# Power_Management.net
KiCad netlist of a schematic drawn in Altium Designer
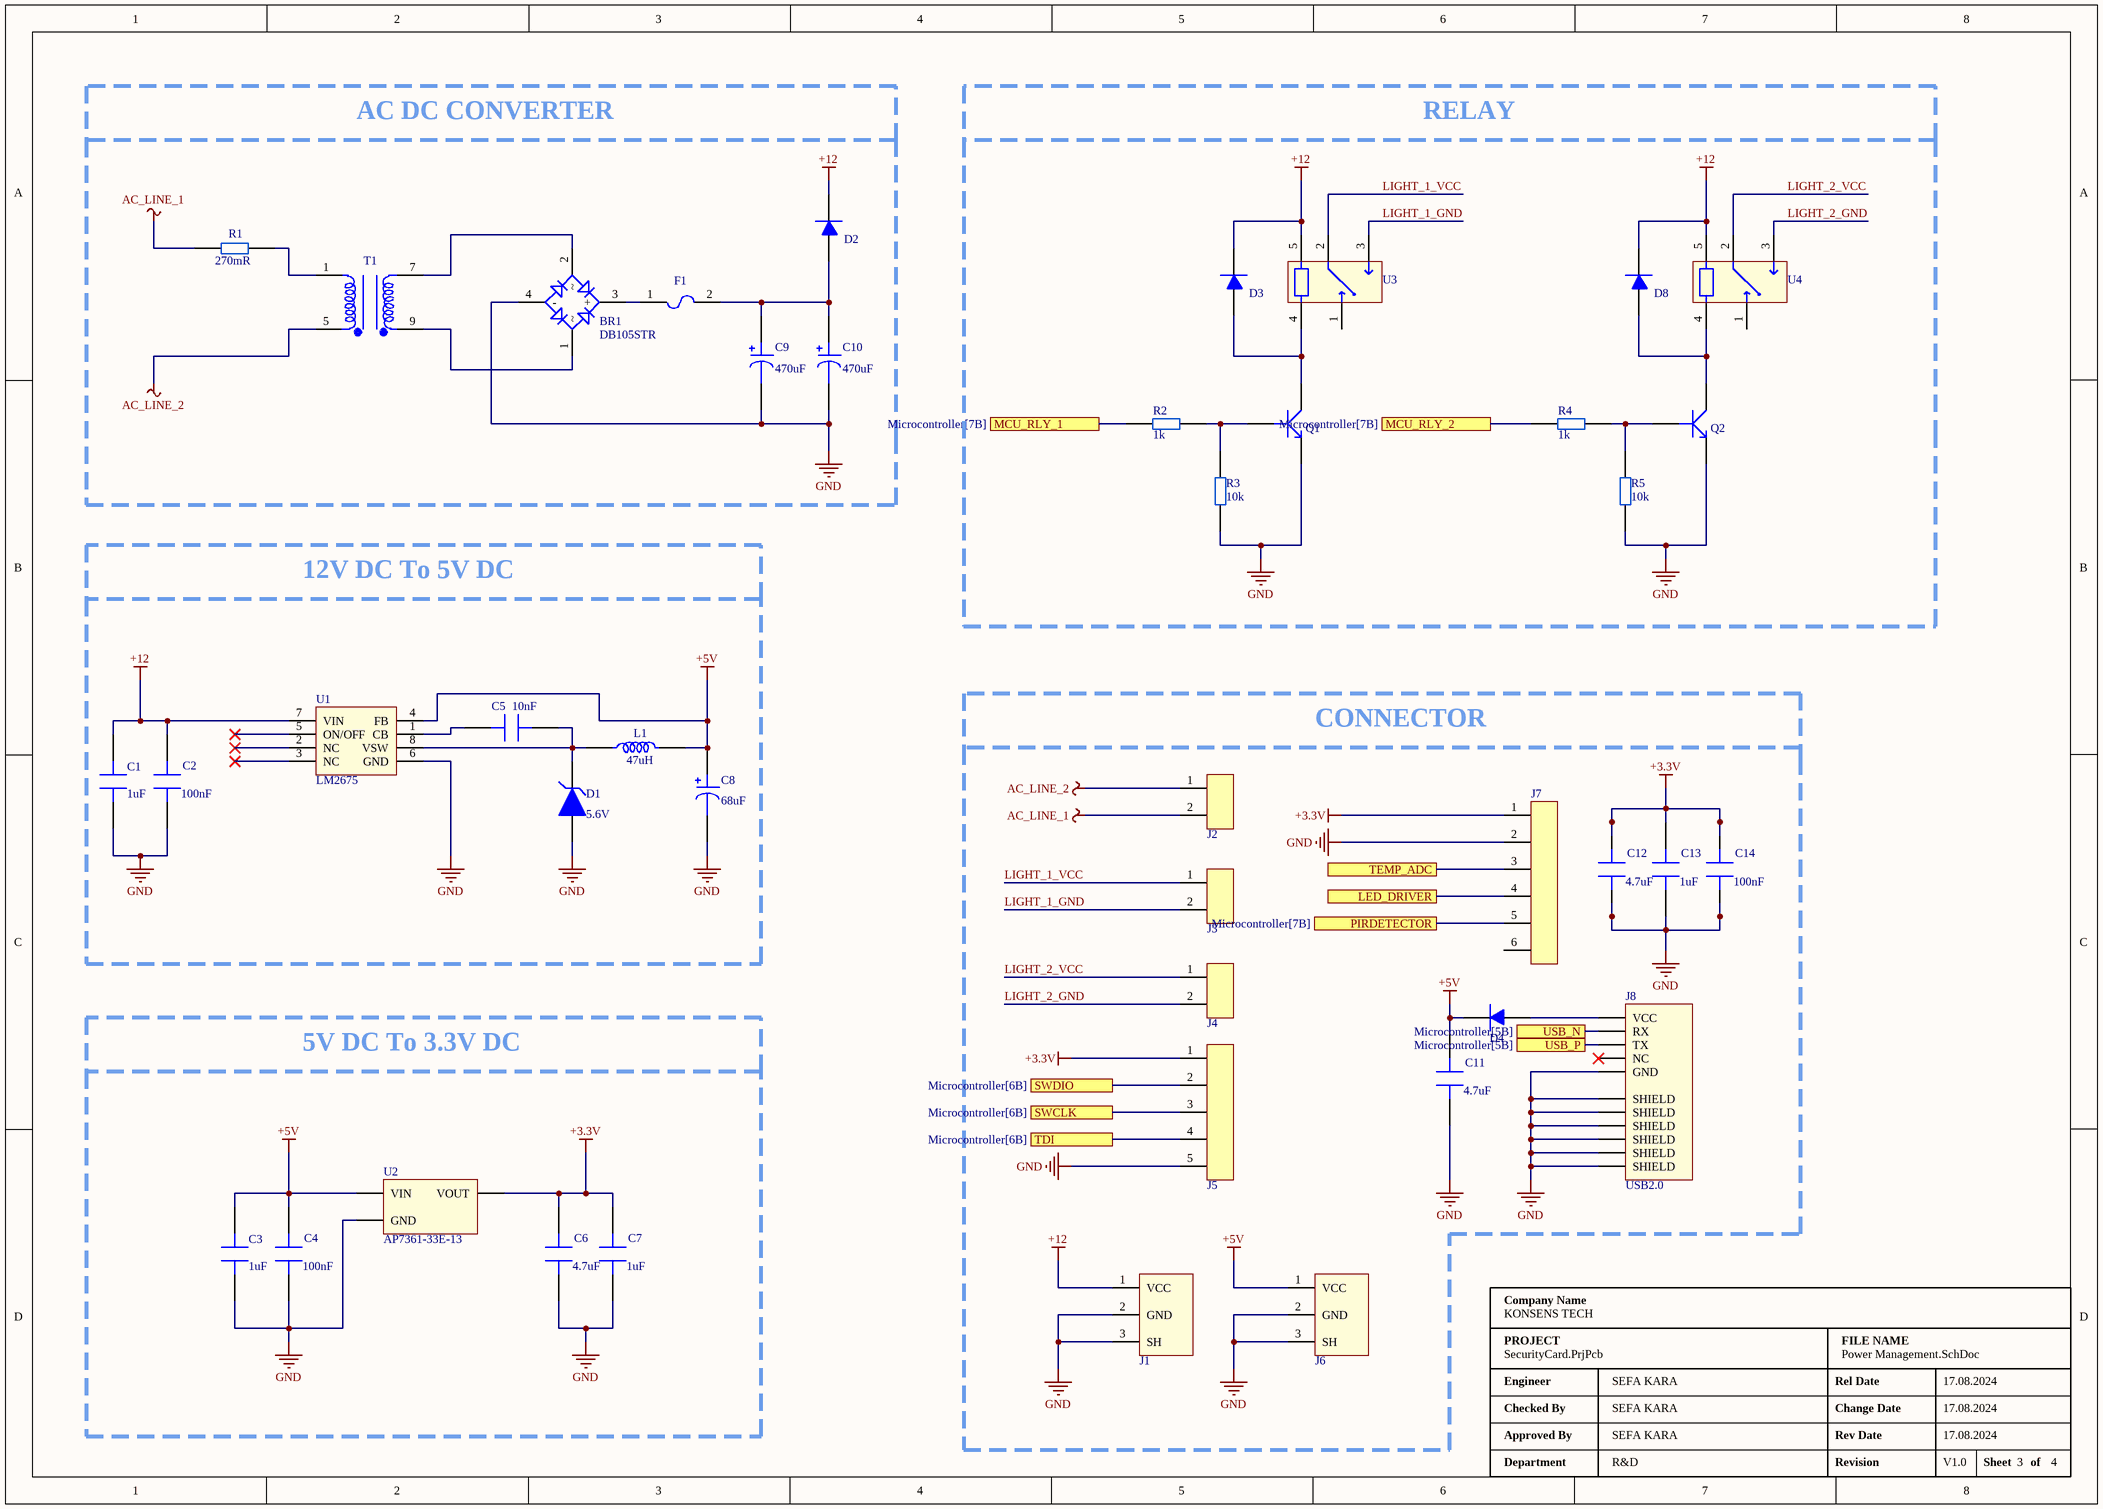
[diagram p0: Power Management.SchDoc]

(export (version "E")
  (design (tool "Eeschema 10.0.6"))
  (components
    (comp (ref "BR1")
      (value "DB105STR")
      (footprint "DB107S")
      (description "Bridge Rect 1PHASE 600V 1A Db-s")
      (fields (field (name "MANUFACTURER") "SMC") (field (name "DESIGNED BY") "SEFA"))
      (libsource (lib "SecurityLibray") (part "DB105STR"))
    )
    (comp (ref "C1")
      (value "1uF")
      (footprint "CAP 0805")
      (description "Multilayer Ceramic Capacitor, 1 uF, 25 V, ï¿½ 10%, X7R, 0805 [2012 Metric]")
      (fields
        (field (name "MANUFACTURER") "KEMET")
        (field (name "MANUFACTURER PART NUMBER") "C0805C105K3RACTU")
      )
      (libsource (lib "SecurityLibray") (part "CAP MLCC 1uF 0805 MLCC"))
    )
    (comp (ref "C2")
      (value "100nF")
      (footprint "CAP 0805")
      (description "Multilayer Ceramic Capacitor, 0.1 uF, 50 V, ± 10%, X7R, 0805 [2012 Metric]")
      (fields
        (field (name "MANUFACTURER") "Yageo")
        (field (name "MANUFACTURER PART NUMBER") "CC0805KRX7R9BB104")
      )
      (libsource (lib "SecurityLibray") (part "CAP MLCC 100nF 0805"))
    )
    (comp (ref "C3")
      (value "1uF")
      (footprint "CAP 0805")
      (description "Multilayer Ceramic Capacitor, 1 uF, 25 V, ï¿½ 10%, X7R, 0805 [2012 Metric]")
      (fields
        (field (name "MANUFACTURER") "KEMET")
        (field (name "MANUFACTURER PART NUMBER") "C0805C105K3RACTU")
      )
      (libsource (lib "SecurityLibray") (part "CAP MLCC 1uF 0805 MLCC"))
    )
    (comp (ref "C4")
      (value "100nF")
      (footprint "CAP 0805")
      (description "Multilayer Ceramic Capacitor, 0.1 uF, 50 V, ± 10%, X7R, 0805 [2012 Metric]")
      (fields
        (field (name "MANUFACTURER") "Yageo")
        (field (name "MANUFACTURER PART NUMBER") "CC0805KRX7R9BB104")
      )
      (libsource (lib "SecurityLibray") (part "CAP MLCC 100nF 0805"))
    )
    (comp (ref "C5")
      (value "10nF")
      (footprint "CAP 0603")
      (description "Multilayer Ceramic Capacitor, 0.01 uF, 50 V, ± 10%, X7R, 0603 [1608 Metric]")
      (fields
        (field (name "MANUFACTURER") "Yageo")
        (field (name "MANUFACTURER PART NUMBER") "CC0603KRX7R9BB103")
        (field (name "DESIGNED BY") "SEFA")
      )
      (libsource (lib "SecurityLibray") (part "CAP MLCC 10nF 0603"))
    )
    (comp (ref "C6")
      (value "4.7uF")
      (footprint "CAP 0805")
      (description "Multilayer Ceramic Capacitor, 4.7 uF, 25 V, ± 10%, X5R, 0805 [2012 Metric]")
      (fields
        (field (name "MANUFACTURER") "Samsung")
        (field (name "MANUFACTURER PART NUMBER") "CL21A475KAQNNNE")
        (field (name "DESIGNED BY") "SEFA")
      )
      (libsource (lib "SecurityLibray") (part "CAP MLCC 4.7uF 0805 MLCC"))
    )
    (comp (ref "C7")
      (value "1uF")
      (footprint "CAP 0805")
      (description "Multilayer Ceramic Capacitor, 1 uF, 25 V, ï¿½ 10%, X7R, 0805 [2012 Metric]")
      (fields
        (field (name "MANUFACTURER") "KEMET")
        (field (name "MANUFACTURER PART NUMBER") "C0805C105K3RACTU")
      )
      (libsource (lib "SecurityLibray") (part "CAP MLCC 1uF 0805 MLCC"))
    )
    (comp (ref "C8")
      (value "68uF")
      (footprint "CAP ALUM 68uF 20% 35V RADIAL TH")
      (description "68 µF 35 V Aluminum Electrolytic Capacitors Radial, Can 2000 Hrs @ 85°C")
      (fields
        (field (name "MANUFACTURER") "Wurth Electronics")
        (field (name "MANUFACTURER PART NUMBER") "860010573006")
        (field (name "DESIGNED BY") "SEFA")
      )
      (libsource (lib "SecurityLibray") (part "CAP 68uF 35V"))
    )
    (comp (ref "C9")
      (value "470uF")
      (footprint "CAP ALUM 470UF 20% 50V RADIAL TH")
      (description "Aluminum Electrolytic Capacitor, 470 uF, 63 V, ± 20%, 8000 hours @ 85°C, Axial Leaded")
      (fields
        (field (name "MANUFACTURER") "Vishay BCcomponents")
        (field (name "MANUFACTURER PART NUMBER") "MAL202118471E3")
      )
      (libsource (lib "SecurityLibray") (part "470uF ECAP CA-1HM471"))
    )
    (comp (ref "C10")
      (value "470uF")
      (footprint "CAP ALUM 470UF 20% 50V RADIAL TH")
      (description "Aluminum Electrolytic Capacitor, 470 uF, 63 V, ± 20%, 8000 hours @ 85°C, Axial Leaded")
      (fields
        (field (name "MANUFACTURER") "Vishay BCcomponents")
        (field (name "MANUFACTURER PART NUMBER") "MAL202118471E3")
      )
      (libsource (lib "SecurityLibray") (part "470uF ECAP CA-1HM471"))
    )
    (comp (ref "C11")
      (value "4.7uF")
      (footprint "CAP 0805")
      (description "Multilayer Ceramic Capacitor, 4.7 uF, 25 V, ± 10%, X5R, 0805 [2012 Metric]")
      (fields
        (field (name "MANUFACTURER") "Samsung")
        (field (name "MANUFACTURER PART NUMBER") "CL21A475KAQNNNE")
        (field (name "DESIGNED BY") "SEFA")
      )
      (libsource (lib "SecurityLibray") (part "CAP MLCC 4.7uF 0805 MLCC"))
    )
    (comp (ref "C12")
      (value "4.7uF")
      (footprint "CAP 0805")
      (description "Multilayer Ceramic Capacitor, 4.7 uF, 25 V, ± 10%, X5R, 0805 [2012 Metric]")
      (fields
        (field (name "MANUFACTURER") "Samsung")
        (field (name "MANUFACTURER PART NUMBER") "CL21A475KAQNNNE")
        (field (name "DESIGNED BY") "SEFA")
      )
      (libsource (lib "SecurityLibray") (part "CAP MLCC 4.7uF 0805 MLCC"))
    )
    (comp (ref "C13")
      (value "1uF")
      (footprint "CAP 0805")
      (description "Multilayer Ceramic Capacitor, 1 uF, 25 V, ï¿½ 10%, X7R, 0805 [2012 Metric]")
      (fields
        (field (name "MANUFACTURER") "KEMET")
        (field (name "MANUFACTURER PART NUMBER") "C0805C105K3RACTU")
      )
      (libsource (lib "SecurityLibray") (part "CAP MLCC 1uF 0805 MLCC"))
    )
    (comp (ref "C14")
      (value "100nF")
      (footprint "CAP 0805")
      (description "Multilayer Ceramic Capacitor, 0.1 uF, 50 V, ± 10%, X7R, 0805 [2012 Metric]")
      (fields
        (field (name "MANUFACTURER") "Yageo")
        (field (name "MANUFACTURER PART NUMBER") "CC0805KRX7R9BB104")
      )
      (libsource (lib "SecurityLibray") (part "CAP MLCC 100nF 0805"))
    )
    (comp (ref "D1")
      (value "DIODE ZENER 5.6V 3W SMB")
      (footprint "SMB")
      (description "Diode Zener Single 5.6V 5% 550mW Automotive 2-Pin SMB T/R")
      (fields
        (field (name "MANUFACTURER") "ON Semiconductor")
        (field (name "MANUFACTURER PART NUMBER") "1SMB5919BT3G")
        (field (name "VOLTAGE RATING (DC)") "5.6V")
        (field (name "DESIGNED BY") "SEFA")
      )
      (libsource (lib "SecurityLibray") (part "1SMB5919BT3G ZENER DIODE"))
    )
    (comp (ref "D2")
      (value "DIODE GEN PURP 75V 150MA SOD323F")
      (footprint "DIODE SOD323F")
      (description "Diode Ultra Fast Recovery Rectifier 75V 0.15A 2-Pin SOD-323F T/R")
      (fields
        (field (name "MANUFACTURER") "ON Semiconductor / Fairchild")
        (field (name "MANUFACTURER PART NUMBER") "1N4148WS")
      )
      (libsource (lib "SecurityLibray") (part "DIODE 1N4148WS"))
    )
    (comp (ref "D3")
      (value "DIODE GEN PURP 75V 150MA SOD323F")
      (footprint "DIODE SOD323F")
      (description "Diode Ultra Fast Recovery Rectifier 75V 0.15A 2-Pin SOD-323F T/R")
      (fields
        (field (name "MANUFACTURER") "ON Semiconductor / Fairchild")
        (field (name "MANUFACTURER PART NUMBER") "1N4148WS")
      )
      (libsource (lib "SecurityLibray") (part "DIODE 1N4148WS"))
    )
    (comp (ref "D4")
      (value "DIODE GEN PURP 75V 150MA SOD323F")
      (footprint "DIODE SOD323F")
      (description "Diode Ultra Fast Recovery Rectifier 75V 0.15A 2-Pin SOD-323F T/R")
      (fields
        (field (name "MANUFACTURER") "ON Semiconductor / Fairchild")
        (field (name "MANUFACTURER PART NUMBER") "1N4148WS")
      )
      (libsource (lib "SecurityLibray") (part "DIODE 1N4148WS"))
    )
    (comp (ref "D8")
      (value "DIODE GEN PURP 75V 150MA SOD323F")
      (footprint "DIODE SOD323F")
      (description "Diode Ultra Fast Recovery Rectifier 75V 0.15A 2-Pin SOD-323F T/R")
      (fields
        (field (name "MANUFACTURER") "ON Semiconductor / Fairchild")
        (field (name "MANUFACTURER PART NUMBER") "1N4148WS")
      )
      (libsource (lib "SecurityLibray") (part "DIODE 1N4148WS"))
    )
    (comp (ref "F1")
      (value "FUSE BRD MNT 1A 32VAC 63VDC 1206")
      (footprint "FUSE 1206 SMD")
      (description "Fuse Chip Fast Acting 1A 32V SMD Solder Pad 1206 Glass T/R VDE/cULus")
      (fields
        (field (name "MANUFACTURER") "Schurter")
        (field (name "MANUFACTURER PART NUMBER") "3413.0216.22")
        (field (name "DESIGNED BY") "SEFA")
      )
      (libsource (lib "SecurityLibray") (part "FUSE 3413.0216.22"))
    )
    (comp (ref "J1")
      (value "CONN PWR JACK 2X5.5MM SOLDER")
      (footprint "POWER JACK")
      (description "2.0 x 6.3 mm, 5.0 A, Horizontal, Surface Mount (SMT), Dc Power Jack Connector")
      (fields
        (field (name "MANUFACTURER") "CUI")
        (field (name "MANUFACTURER PART NUMBER") "PJ-037AH-SMT-TR")
        (field (name "DESIGNED BY") "SEFA")
      )
      (libsource (lib "SecurityLibray") (part "JACK CONN PJ-037AH-SMT-TR"))
    )
    (comp (ref "J2")
      (value "TERMINAL BLOCK, PLUGGABLE, 5.08,")
      (footprint "TERMINAL 2P 508")
      (description "2~24 Poles, Pluggable, Receptacle, Horizontal, 5.08 Pitch, Terminal Block Connector")
      (fields
        (field (name "MANUFACTURER") "CUI Devices")
        (field (name "MANUFACTURER PART NUMBER") "TBP01R1-508-02BE")
        (field (name "DESIGNED BY") "SEFA")
      )
      (libsource (lib "SecurityLibray") (part "2P TERMINAL TBP01R1-508-02BE"))
    )
    (comp (ref "J3")
      (value "TERMINAL BLOCK, PLUGGABLE, 5.08,")
      (footprint "TERMINAL 2P 508")
      (description "2~24 Poles, Pluggable, Receptacle, Horizontal, 5.08 Pitch, Terminal Block Connector")
      (fields
        (field (name "MANUFACTURER") "CUI Devices")
        (field (name "MANUFACTURER PART NUMBER") "TBP01R1-508-02BE")
        (field (name "DESIGNED BY") "SEFA")
      )
      (libsource (lib "SecurityLibray") (part "2P TERMINAL TBP01R1-508-02BE"))
    )
    (comp (ref "J4")
      (value "TERMINAL BLOCK, PLUGGABLE, 5.08,")
      (footprint "TERMINAL 2P 508")
      (description "2~24 Poles, Pluggable, Receptacle, Horizontal, 5.08 Pitch, Terminal Block Connector")
      (fields
        (field (name "MANUFACTURER") "CUI Devices")
        (field (name "MANUFACTURER PART NUMBER") "TBP01R1-508-02BE")
        (field (name "DESIGNED BY") "SEFA")
      )
      (libsource (lib "SecurityLibray") (part "2P TERMINAL TBP01R1-508-02BE"))
    )
    (comp (ref "J5")
      (value "CONN RCPT 5POS 0.1 GOLD SMD R/A")
      (footprint "PIN HEADER 5P 2.54mm MH-105-02-L-S")
      (description "PCB Receptacle, Board-to-Board, 2.54 mm, 1 Rows, 5 Contacts, Surface Mount, SMH")
      (fields
        (field (name "MANUFACTURER") "Samtec")
        (field (name "MANUFACTURER PART NUMBER") "SMH-105-02-L-S")
        (field (name "DESIGNED BY") "SEFA")
      )
      (libsource (lib "SecurityLibray") (part "PIN HEADER 2.54mm SMH-105-02-L-S"))
    )
    (comp (ref "J6")
      (value "CONN PWR JACK 2X5.5MM SOLDER")
      (footprint "POWER JACK")
      (description "2.0 x 6.3 mm, 5.0 A, Horizontal, Surface Mount (SMT), Dc Power Jack Connector")
      (fields
        (field (name "MANUFACTURER") "CUI")
        (field (name "MANUFACTURER PART NUMBER") "PJ-037AH-SMT-TR")
        (field (name "DESIGNED BY") "SEFA")
      )
      (libsource (lib "SecurityLibray") (part "JACK CONN PJ-037AH-SMT-TR"))
    )
    (comp (ref "J7")
      (value "CONN HEADER VERT 6POS 1.5MM")
      (footprint "TUNIK 6P 2.5mm")
      (description "Header B6B-ZR, 1.50mm, 6-contacts, top entry, THT, /2000/box")
      (fields
        (field (name "MANUFACTURER") "JST")
        (field (name "MANUFACTURER PART NUMBER") "B6B-ZR")
        (field (name "DESIGNED BY") "SEFA")
      )
      (libsource (lib "SecurityLibray") (part "TUNIK 6P 2.5mm"))
    )
    (comp (ref "J8")
      (value "USB2.0")
      (footprint "MICRO B USB CONN")
      (description "CONN USB MICRO B RECPT SMT R/A")
      (fields
        (field (name "MANUFACTURER") "Amphenol ICC / FCI")
        (field (name "MANUFACTURER PART NUMBER") "10118192-0001LF")
        (field (name "DESIGNED BY") "SEFA")
      )
      (libsource (lib "SecurityLibray") (part "MICRO B USB CONN"))
    )
    (comp (ref "L1")
      (value "47uH")
      (footprint "IND 1212")
      (description "Power Inductor, Aec-Q200, 47Uh, 0.39A Rohs Compliant: Yes ¦Wurth Elektronik 78438335470")
      (fields
        (field (name "MANUFACTURER") "Wurth Electronics")
        (field (name "MANUFACTURER PART NUMBER") "78438335470")
        (field (name "DESIGNED BY") "SEFA")
      )
      (libsource (lib "SecurityLibray") (part "IND 47uH"))
    )
    (comp (ref "Q1")
      (value "TRANS NPN 40V 0.2A SOT23")
      (footprint "SOT-23-3")
      (description "Transistor: NPN; bipolar; 40V; 0.2A; 350mW; -55+150 deg.C; SMD; SOT23")
      (fields
        (field (name "MANUFACTURER") "Diotec")
        (field (name "MANUFACTURER PART NUMBER") "MMBT3904")
        (field (name "DESIGNED BY") "SEFA")
      )
      (libsource (lib "SecurityLibray") (part "MMBT3904 NPN TR"))
    )
    (comp (ref "Q2")
      (value "TRANS NPN 40V 0.2A SOT23")
      (footprint "SOT-23-3")
      (description "Transistor: NPN; bipolar; 40V; 0.2A; 350mW; -55+150 deg.C; SMD; SOT23")
      (fields
        (field (name "MANUFACTURER") "Diotec")
        (field (name "MANUFACTURER PART NUMBER") "MMBT3904")
        (field (name "DESIGNED BY") "SEFA")
      )
      (libsource (lib "SecurityLibray") (part "MMBT3904 NPN TR"))
    )
    (comp (ref "R1")
      (value "270mR")
      (footprint "SQP500JB-10R")
      (description "270 mOhms ±5% 5W Through Hole Resistor Axial Wirewound")
      (fields (field (name "Comment") "RES 0.27 OHM 5% 5W AXIAL"))
      (libsource (lib "SecurityLibray") (part "RES 270mR 5WD27"))
    )
    (comp (ref "R2")
      (value "1k")
      (footprint "RES 0603")
      (description "Res Thick Film 0603 10K Ohm 5% 1/10W ±100ppm/°C Molded SMD SMD Paper T/R")
      (fields
        (field (name "MANUFACTURER") "Stackpole Electronics")
        (field (name "MANUFACTURER PART NUMBER") "RMCF0603JT10K0")
        (field (name "DESIGNED BY") "SEFA")
      )
      (libsource (lib "") (part "RES 10K OHM 0603_1"))
    )
    (comp (ref "R3")
      (value "10k")
      (footprint "RES 0603")
      (description "Res Thick Film 0603 10K Ohm 5% 1/10W ±100ppm/°C Molded SMD SMD Paper T/R")
      (fields
        (field (name "MANUFACTURER") "Stackpole Electronics")
        (field (name "MANUFACTURER PART NUMBER") "RMCF0603JT10K0")
        (field (name "DESIGNED BY") "SEFA")
      )
      (libsource (lib "SecurityLibray") (part "RES 10K OHM 0603"))
    )
    (comp (ref "R4")
      (value "1k")
      (footprint "RES 0603")
      (description "Res Thick Film 0603 10K Ohm 5% 1/10W ±100ppm/°C Molded SMD SMD Paper T/R")
      (fields
        (field (name "MANUFACTURER") "Stackpole Electronics")
        (field (name "MANUFACTURER PART NUMBER") "RMCF0603JT10K0")
        (field (name "DESIGNED BY") "SEFA")
      )
      (libsource (lib "") (part "RES 10K OHM 0603_1"))
    )
    (comp (ref "R5")
      (value "10k")
      (footprint "RES 0603")
      (description "Res Thick Film 0603 10K Ohm 5% 1/10W ±100ppm/°C Molded SMD SMD Paper T/R")
      (fields
        (field (name "MANUFACTURER") "Stackpole Electronics")
        (field (name "MANUFACTURER PART NUMBER") "RMCF0603JT10K0")
        (field (name "DESIGNED BY") "SEFA")
      )
      (libsource (lib "SecurityLibray") (part "RES 10K OHM 0603"))
    )
    (comp (ref "T1")
      (value "BV302S12010-ZU")
      (footprint "BV302S")
      (description "Sealed Transformer EI30/10.5")
      (fields
        (field (name "MANUFACTURER") "Zettler Magnetics")
        (field (name "MANUFACTURER PART NUMBER") "BV302S12010")
      )
      (libsource (lib "SecurityLibray") (part "BV302S12010-ZU"))
    )
    (comp (ref "U1")
      (value "LM2675")
      (footprint "SOIC8")
      (description "SIMPLE SWITCHER® 6.5V to 40V, 1A Low Component Count Step-Down Regulator 8-SOIC -40 to 125")
      (fields
        (field (name "MANUFACTURER") "TI National Semiconductor")
        (field (name "MANUFACTURER PART NUMBER") "LM2675M-5.0")
        (field (name "DESIGNED BY") "SEFA")
      )
      (libsource (lib "SecurityLibray") (part "LM2675"))
    )
    (comp (ref "U2")
      (value "AP7361-33E-13")
      (footprint "SOT223")
      (description "AP7361 Series 3.3 V 1 A Low SMT Dropout Fixed-Mode Regulator - SOT-223")
      (fields (field (name "MANUFACTURER") "Diodes") (field (name "DESIGNED BY") "SEFA"))
      (libsource (lib "SecurityLibray") (part "AP7361-33E-13"))
    )
    (comp (ref "U3")
      (value "ALQ112")
      (footprint "RELAY ALQ112")
      (description "Electromechanical Relay 12VDC 360Ohm 10(NO)/3(NC)A SPDT (( 20mm 10mm 16mm)) THT Power Relay")
      (fields (field (name "MANUFACTURER") "Panasonic") (field (name "DESIGNED BY") "SEFA"))
      (libsource (lib "SecurityLibray") (part "ALQ112"))
    )
    (comp (ref "U4")
      (value "ALQ112")
      (footprint "RELAY ALQ112")
      (description "Electromechanical Relay 12VDC 360Ohm 10(NO)/3(NC)A SPDT (( 20mm 10mm 16mm)) THT Power Relay")
      (fields (field (name "MANUFACTURER") "Panasonic") (field (name "DESIGNED BY") "SEFA"))
      (libsource (lib "SecurityLibray") (part "ALQ112"))
    )
  )
  (nets
    (net (code "1") (name "+3.3V") (class "Default")
      (node (ref "C12") (pin "2") (pinfunction "2_2") (pintype "passive"))
      (node (ref "C13") (pin "2") (pinfunction "2_2") (pintype "passive"))
      (node (ref "C14") (pin "2") (pinfunction "2_2") (pintype "passive"))
      (node (ref "C6") (pin "1") (pinfunction "1_1") (pintype "passive"))
      (node (ref "C7") (pin "2") (pinfunction "2_2") (pintype "passive"))
      (node (ref "J5") (pin "1") (pinfunction "1_1") (pintype "passive"))
      (node (ref "J7") (pin "1") (pintype "passive"))
      (node (ref "U2") (pin "3") (pinfunction "VOUT_3") (pintype "passive"))
    )
    (net (code "2") (name "+5V") (class "Default")
      (node (ref "C11") (pin "2") (pinfunction "2_2") (pintype "passive"))
      (node (ref "C3") (pin "2") (pinfunction "2_2") (pintype "passive"))
      (node (ref "C4") (pin "2") (pinfunction "2_2") (pintype "passive"))
      (node (ref "C8") (pin "1") (pinfunction "1_1") (pintype "passive"))
      (node (ref "D4") (pin "C") (pinfunction "2_C") (pintype "passive"))
      (node (ref "J6") (pin "1") (pinfunction "VCC_1") (pintype "passive"))
      (node (ref "L1") (pin "2") (pinfunction "2_2") (pintype "passive"))
      (node (ref "U1") (pin "4") (pinfunction "FB_4") (pintype "passive"))
      (node (ref "U2") (pin "1") (pinfunction "VIN_1") (pintype "passive"))
    )
    (net (code "3") (name "+12") (class "Default")
      (node (ref "C1") (pin "2") (pinfunction "2_2") (pintype "passive"))
      (node (ref "C2") (pin "2") (pinfunction "2_2") (pintype "passive"))
      (node (ref "D2") (pin "C") (pinfunction "2_C") (pintype "passive"))
      (node (ref "D3") (pin "C") (pinfunction "2_C") (pintype "passive"))
      (node (ref "D8") (pin "C") (pinfunction "2_C") (pintype "passive"))
      (node (ref "J1") (pin "1") (pinfunction "VCC_1") (pintype "passive"))
      (node (ref "U1") (pin "7") (pinfunction "VIN_7") (pintype "passive"))
      (node (ref "U3") (pin "5") (pinfunction "5_5") (pintype "passive"))
      (node (ref "U4") (pin "5") (pinfunction "5_5") (pintype "passive"))
    )
    (net (code "4") (name "/LED_DRIVER") (class "Default") (node (ref "J7") (pin "4") (pintype "passive")))
    (net (code "5") (name "/LIGHT_1_GND") (class "Default")
      (node (ref "J3") (pin "2") (pinfunction "2_2") (pintype "passive"))
      (node (ref "U3") (pin "3") (pinfunction "3_3") (pintype "passive"))
    )
    (net (code "6") (name "/LIGHT_1_VCC") (class "Default")
      (node (ref "J3") (pin "1") (pinfunction "1_1") (pintype "passive"))
      (node (ref "U3") (pin "2") (pinfunction "2_2") (pintype "passive"))
    )
    (net (code "7") (name "/LIGHT_2_GND") (class "Default")
      (node (ref "J4") (pin "2") (pinfunction "2_2") (pintype "passive"))
      (node (ref "U4") (pin "3") (pinfunction "3_3") (pintype "passive"))
    )
    (net (code "8") (name "/LIGHT_2_VCC") (class "Default")
      (node (ref "J4") (pin "1") (pinfunction "1_1") (pintype "passive"))
      (node (ref "U4") (pin "2") (pinfunction "2_2") (pintype "passive"))
    )
    (net (code "9") (name "/MCU_RLY_1") (class "Default")
      (node (ref "R2") (pin "2") (pinfunction "2_2") (pintype "passive"))
    )
    (net (code "10") (name "/MCU_RLY_2") (class "Default")
      (node (ref "R4") (pin "2") (pinfunction "2_2") (pintype "passive"))
    )
    (net (code "11") (name "/PIRDETECTOR") (class "Default") (node (ref "J7") (pin "5") (pintype "passive")))
    (net (code "12") (name "/SWCLK") (class "Default")
      (node (ref "J5") (pin "3") (pinfunction "3_3") (pintype "passive"))
    )
    (net (code "13") (name "/SWDIO") (class "Default")
      (node (ref "J5") (pin "2") (pinfunction "2_2") (pintype "passive"))
    )
    (net (code "14") (name "/TDI") (class "Default")
      (node (ref "J5") (pin "4") (pinfunction "4_4") (pintype "passive"))
    )
    (net (code "15") (name "/TEMP_ADC") (class "Default") (node (ref "J7") (pin "3") (pintype "passive")))
    (net (code "16") (name "/USB_N") (class "Default")
      (node (ref "J8") (pin "2") (pinfunction "RX_2") (pintype "passive"))
    )
    (net (code "17") (name "/USB_P") (class "Default")
      (node (ref "J8") (pin "3") (pinfunction "TX_3") (pintype "passive"))
    )
    (net (code "18") (name "AC_LINE_1") (class "Default")
      (node (ref "J2") (pin "2") (pinfunction "2_2") (pintype "passive"))
      (node (ref "R1") (pin "1") (pinfunction "1_1") (pintype "passive"))
    )
    (net (code "19") (name "AC_LINE_2") (class "Default")
      (node (ref "J2") (pin "1") (pinfunction "1_1") (pintype "passive"))
      (node (ref "T1") (pin "5") (pinfunction "5_5") (pintype "passive"))
    )
    (net (code "20") (name "GND") (class "Default")
      (node (ref "BR1") (pin "4") (pinfunction "-_4") (pintype "passive"))
      (node (ref "C1") (pin "1") (pinfunction "1_1") (pintype "passive"))
      (node (ref "C10") (pin "2") (pinfunction "2_2") (pintype "passive"))
      (node (ref "C11") (pin "1") (pinfunction "1_1") (pintype "passive"))
      (node (ref "C12") (pin "1") (pinfunction "1_1") (pintype "passive"))
      (node (ref "C13") (pin "1") (pinfunction "1_1") (pintype "passive"))
      (node (ref "C14") (pin "1") (pinfunction "1_1") (pintype "passive"))
      (node (ref "C2") (pin "1") (pinfunction "1_1") (pintype "passive"))
      (node (ref "C3") (pin "1") (pinfunction "1_1") (pintype "passive"))
      (node (ref "C4") (pin "1") (pinfunction "1_1") (pintype "passive"))
      (node (ref "C6") (pin "2") (pinfunction "2_2") (pintype "passive"))
      (node (ref "C7") (pin "1") (pinfunction "1_1") (pintype "passive"))
      (node (ref "C8") (pin "2") (pinfunction "2_2") (pintype "passive"))
      (node (ref "C9") (pin "2") (pinfunction "2_2") (pintype "passive"))
      (node (ref "D1") (pin "A") (pinfunction "A_A") (pintype "passive"))
      (node (ref "J1") (pin "2") (pinfunction "GND_2") (pintype "passive"))
      (node (ref "J1") (pin "3") (pinfunction "SH_3") (pintype "passive"))
      (node (ref "J5") (pin "5") (pinfunction "5_5") (pintype "passive"))
      (node (ref "J6") (pin "2") (pinfunction "GND_2") (pintype "passive"))
      (node (ref "J6") (pin "3") (pinfunction "SH_3") (pintype "passive"))
      (node (ref "J7") (pin "2") (pintype "passive"))
      (node (ref "J8") (pin "5") (pinfunction "GND_5") (pintype "passive"))
      (node (ref "J8") (pin "SH1") (pinfunction "SHIELD_SH1") (pintype "passive"))
      (node (ref "J8") (pin "SH2") (pinfunction "SHIELD_SH2") (pintype "passive"))
      (node (ref "J8") (pin "SH3") (pinfunction "SHIELD_SH3") (pintype "passive"))
      (node (ref "J8") (pin "SH4") (pinfunction "SHIELD_SH4") (pintype "passive"))
      (node (ref "J8") (pin "SH5") (pinfunction "SHIELD_SH5") (pintype "passive"))
      (node (ref "J8") (pin "SH6") (pinfunction "SHIELD_SH6") (pintype "passive"))
      (node (ref "Q1") (pin "2") (pinfunction "E_2") (pintype "passive"))
      (node (ref "Q2") (pin "2") (pinfunction "E_2") (pintype "passive"))
      (node (ref "R3") (pin "1") (pinfunction "1_1") (pintype "passive"))
      (node (ref "R5") (pin "1") (pinfunction "1_1") (pintype "passive"))
      (node (ref "U1") (pin "6") (pinfunction "GND_6") (pintype "passive"))
      (node (ref "U2") (pin "2") (pinfunction "GND_2") (pintype "passive"))
    )
    (net (code "21") (name "Net-(BR1-+)") (class "Default")
      (node (ref "BR1") (pin "3") (pinfunction "+_3") (pintype "passive"))
      (node (ref "F1") (pin "1") (pinfunction "1_1") (pintype "passive"))
    )
    (net (code "22") (name "Net-(BR1-~-Pad1)") (class "Default")
      (node (ref "BR1") (pin "1") (pinfunction "~_1") (pintype "passive"))
      (node (ref "T1") (pin "9") (pinfunction "9_9") (pintype "passive"))
    )
    (net (code "23") (name "Net-(BR1-~-Pad2)") (class "Default")
      (node (ref "BR1") (pin "2") (pinfunction "~_2") (pintype "passive"))
      (node (ref "T1") (pin "7") (pinfunction "7_7") (pintype "passive"))
    )
    (net (code "24") (name "Net-(D2-1)") (class "Default")
      (node (ref "C10") (pin "1") (pinfunction "1_1") (pintype "passive"))
      (node (ref "C9") (pin "1") (pinfunction "1_1") (pintype "passive"))
      (node (ref "D2") (pin "A") (pinfunction "1_A") (pintype "passive"))
      (node (ref "F1") (pin "2") (pinfunction "2_2") (pintype "passive"))
    )
    (net (code "25") (name "Net-(D3-1)") (class "Default")
      (node (ref "D3") (pin "A") (pinfunction "1_A") (pintype "passive"))
      (node (ref "Q1") (pin "3") (pinfunction "C_3") (pintype "passive"))
      (node (ref "U3") (pin "4") (pinfunction "4_4") (pintype "passive"))
    )
    (net (code "26") (name "Net-(D4-1)") (class "Default")
      (node (ref "D4") (pin "A") (pinfunction "1_A") (pintype "passive"))
      (node (ref "J8") (pin "1") (pinfunction "VCC_1") (pintype "passive"))
    )
    (net (code "27") (name "Net-(D8-1)") (class "Default")
      (node (ref "D8") (pin "A") (pinfunction "1_A") (pintype "passive"))
      (node (ref "Q2") (pin "3") (pinfunction "C_3") (pintype "passive"))
      (node (ref "U4") (pin "4") (pinfunction "4_4") (pintype "passive"))
    )
    (net (code "28") (name "Net-(Q1-B)") (class "Default")
      (node (ref "Q1") (pin "1") (pinfunction "B_1") (pintype "passive"))
      (node (ref "R2") (pin "1") (pinfunction "1_1") (pintype "passive"))
      (node (ref "R3") (pin "2") (pinfunction "2_2") (pintype "passive"))
    )
    (net (code "29") (name "Net-(Q2-B)") (class "Default")
      (node (ref "Q2") (pin "1") (pinfunction "B_1") (pintype "passive"))
      (node (ref "R4") (pin "1") (pinfunction "1_1") (pintype "passive"))
      (node (ref "R5") (pin "2") (pinfunction "2_2") (pintype "passive"))
    )
    (net (code "30") (name "Net-(R1-Pad2)") (class "Default")
      (node (ref "R1") (pin "2") (pinfunction "2_2") (pintype "passive"))
      (node (ref "T1") (pin "1") (pinfunction "1_1") (pintype "passive"))
    )
    (net (code "31") (name "Net-(U1-CB)") (class "Default")
      (node (ref "C5") (pin "1") (pinfunction "1_1") (pintype "passive"))
      (node (ref "U1") (pin "1") (pinfunction "CB_1") (pintype "passive"))
    )
    (net (code "32") (name "Net-(U1-VSW)") (class "Default")
      (node (ref "C5") (pin "2") (pinfunction "2_2") (pintype "passive"))
      (node (ref "D1") (pin "C") (pinfunction "C_C") (pintype "passive"))
      (node (ref "L1") (pin "1") (pinfunction "1_1") (pintype "passive"))
      (node (ref "U1") (pin "8") (pinfunction "VSW_8") (pintype "passive"))
    )
    (net (code "33") (name "unconnected-(J7-Pad6)") (class "Default")
      (node (ref "J7") (pin "6") (pintype "passive"))
    )
    (net (code "34") (name "unconnected-(J8-NC-Pad4)") (class "Default")
      (node (ref "J8") (pin "4") (pinfunction "NC_4") (pintype "passive+no_connect"))
    )
    (net (code "35") (name "unconnected-(U1-NC-Pad2)") (class "Default")
      (node (ref "U1") (pin "2") (pinfunction "NC_2") (pintype "passive+no_connect"))
    )
    (net (code "36") (name "unconnected-(U1-NC-Pad3)") (class "Default")
      (node (ref "U1") (pin "3") (pinfunction "NC_3") (pintype "passive+no_connect"))
    )
    (net (code "37") (name "unconnected-(U1-ON{slash}OFF-Pad5)") (class "Default")
      (node (ref "U1") (pin "5") (pinfunction "ON/OFF_5") (pintype "passive+no_connect"))
    )
    (net (code "38") (name "unconnected-(U3-Pad1)") (class "Default")
      (node (ref "U3") (pin "1") (pinfunction "1_1") (pintype "passive"))
    )
    (net (code "39") (name "unconnected-(U4-Pad1)") (class "Default")
      (node (ref "U4") (pin "1") (pinfunction "1_1") (pintype "passive"))
    )
  )
)
